# Netzteil.net
KiCad netlist of a schematic drawn in EAGLE
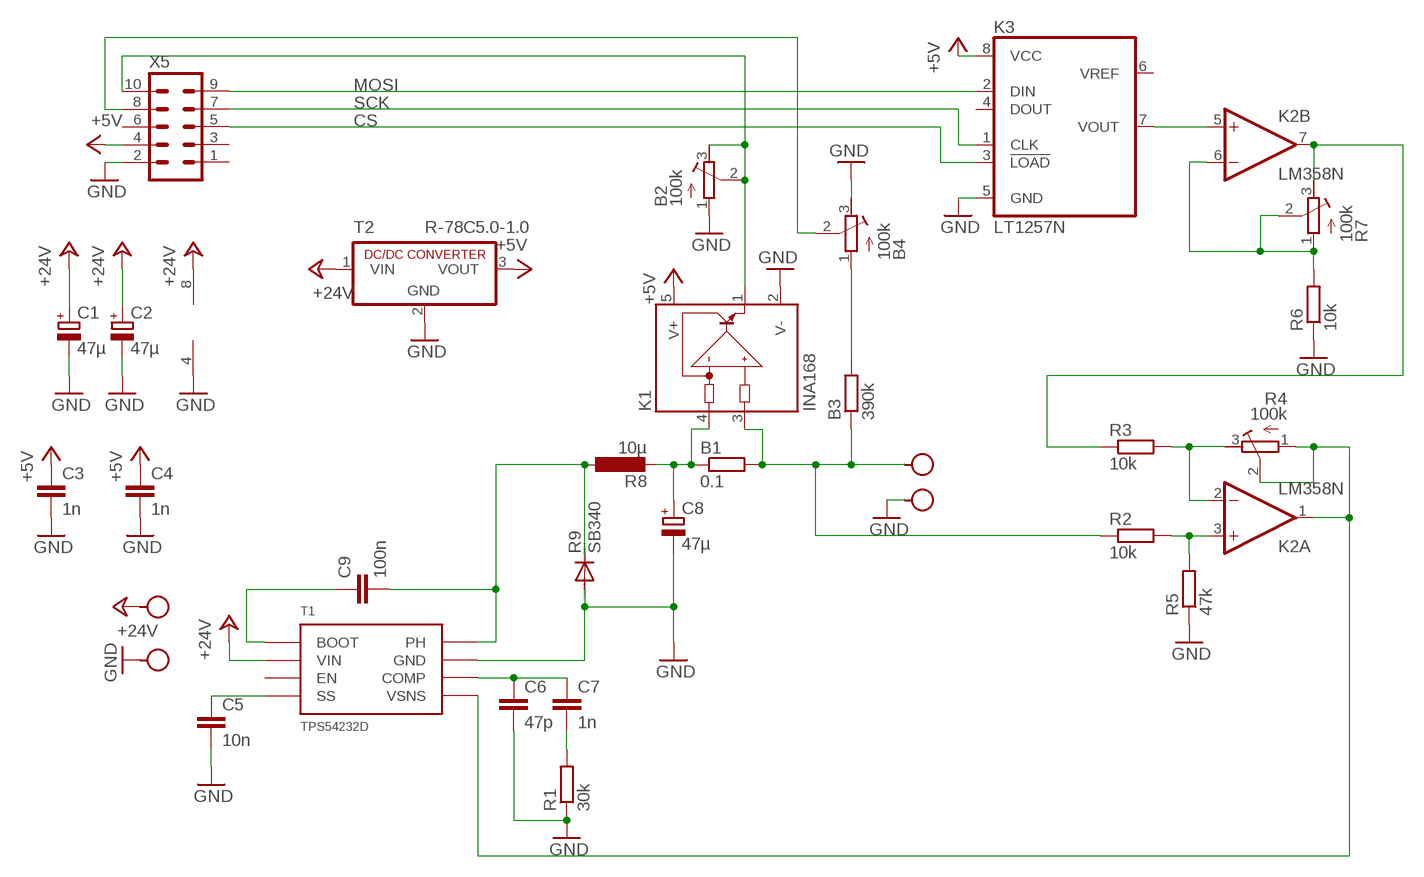
[diagram p0: schematic, sheet 1]

(export (version "E")
  (design (tool "Eeschema 10.0.6"))
  (components
    (comp (ref "B1")
      (value "0.1")
      (footprint "eagle-import:P0817_22")
      (libsource (lib "eagle-import") (part "R-EU_0817/22"))
    )
    (comp (ref "B2")
      (value "100k")
      (footprint "eagle-import:RTRIM64Y")
      (libsource (lib "eagle-import") (part "R-TRIMM64Y"))
    )
    (comp (ref "B3")
      (value "390k")
      (footprint "eagle-import:0309_12")
      (libsource (lib "eagle-import") (part "R-EU_0309/12"))
    )
    (comp (ref "B4")
      (value "100k")
      (footprint "eagle-import:RTRIM64Y")
      (libsource (lib "eagle-import") (part "R-TRIMM64Y"))
    )
    (comp (ref "C1")
      (value "47µ")
      (footprint "eagle-import:E2,5-6")
      (libsource (lib "eagle-import") (part "CPOL-EUE2.5-6"))
    )
    (comp (ref "C2")
      (value "47µ")
      (footprint "eagle-import:E2,5-6")
      (libsource (lib "eagle-import") (part "CPOL-EUE2.5-6"))
    )
    (comp (ref "C3")
      (value "1n")
      (footprint "eagle-import:C025-025X050")
      (libsource (lib "eagle-import") (part "C-EU025-025X050"))
    )
    (comp (ref "C4")
      (value "1n")
      (footprint "eagle-import:C025-025X050")
      (libsource (lib "eagle-import") (part "C-EU025-025X050"))
    )
    (comp (ref "C5")
      (value "10n")
      (footprint "eagle-import:C025-025X050")
      (libsource (lib "eagle-import") (part "C-EU025-025X050"))
    )
    (comp (ref "C6")
      (value "47p")
      (footprint "eagle-import:C025-025X050")
      (libsource (lib "eagle-import") (part "C-EU025-025X050"))
    )
    (comp (ref "C7")
      (value "1n")
      (footprint "eagle-import:C025-025X050")
      (libsource (lib "eagle-import") (part "C-EU025-025X050"))
    )
    (comp (ref "C8")
      (value "47µ")
      (footprint "eagle-import:E2,5-6")
      (libsource (lib "eagle-import") (part "CPOL-EUE2.5-6"))
    )
    (comp (ref "C9")
      (value "100n")
      (footprint "eagle-import:C025-025X050")
      (libsource (lib "eagle-import") (part "C-EU025-025X050"))
    )
    (comp (ref "K1")
      (value "INA168")
      (footprint "eagle-import:SOT23-5")
      (fields (field (name "MF") "TEXAS INSTRUMENTS") (field (name "MPN") "INA168NA/250"))
      (libsource (lib "eagle-import") (part "INA168"))
    )
    (comp (ref "K2")
      (value "LM358N")
      (footprint "eagle-import:DIL08")
      (libsource (lib "eagle-import") (part "LM358N"))
    )
    (comp (ref "K3")
      (value "LT1257N")
      (footprint "eagle-import:DIL08")
      (libsource (lib "eagle-import") (part "LT1257N"))
    )
    (comp (ref "R1")
      (value "30k")
      (footprint "eagle-import:0309_12")
      (libsource (lib "eagle-import") (part "R-EU_0309/12"))
    )
    (comp (ref "R2")
      (value "10k")
      (footprint "eagle-import:0309_12")
      (libsource (lib "eagle-import") (part "R-EU_0309/12"))
    )
    (comp (ref "R3")
      (value "10k")
      (footprint "eagle-import:0309_12")
      (libsource (lib "eagle-import") (part "R-EU_0309/12"))
    )
    (comp (ref "R4")
      (value "100k")
      (footprint "eagle-import:RTRIM64Y")
      (libsource (lib "eagle-import") (part "R-TRIMM64Y"))
    )
    (comp (ref "R5")
      (value "47k")
      (footprint "eagle-import:0309_12")
      (libsource (lib "eagle-import") (part "R-EU_0309/12"))
    )
    (comp (ref "R6")
      (value "10k")
      (footprint "eagle-import:0309_12")
      (libsource (lib "eagle-import") (part "R-EU_0309/12"))
    )
    (comp (ref "R7")
      (value "100k")
      (footprint "eagle-import:RTRIM64Y")
      (libsource (lib "eagle-import") (part "R-TRIMM64Y"))
    )
    (comp (ref "R8")
      (value "10µ")
      (footprint "eagle-import:PIS2816")
      (libsource (lib "eagle-import") (part "L-EUPIS2816"))
    )
    (comp (ref "R9")
      (value "SB340")
      (footprint "eagle-import:DO201-15")
      (libsource (lib "eagle-import") (part "SB320"))
    )
    (comp (ref "T1")
      (value "TPS54232D")
      (footprint "eagle-import:SOIC-8")
      (fields (field (name "MANUFACTURER") "Texas Instruments") (field (name "PART_NUMBER") "TPS54331DR"))
      (libsource (lib "eagle-import") (part "TPS54331DR"))
    )
    (comp (ref "T2")
      (value "R-78C5.0-1.0")
      (footprint "eagle-import:SIP3")
      (fields (field (name "MF") "RECOM POWER"))
      (libsource (lib "eagle-import") (part "R-78C-1.05.0"))
    )
    (comp (ref "X1")
      (value "SEW_HOLE-SMALL")
      (footprint "eagle-import:SIMPLE_HOLE_SM")
      (libsource (lib "eagle-import") (part "SEW_HOLE-SMALL"))
    )
    (comp (ref "X2")
      (value "SEW_HOLE-SMALL")
      (footprint "eagle-import:SIMPLE_HOLE_SM")
      (libsource (lib "eagle-import") (part "SEW_HOLE-SMALL"))
    )
    (comp (ref "X3")
      (value "SEW_HOLE-SMALL")
      (footprint "eagle-import:SIMPLE_HOLE_SM")
      (libsource (lib "eagle-import") (part "SEW_HOLE-SMALL"))
    )
    (comp (ref "X4")
      (value "SEW_HOLE-SMALL")
      (footprint "eagle-import:SIMPLE_HOLE_SM")
      (libsource (lib "eagle-import") (part "SEW_HOLE-SMALL"))
    )
    (comp (ref "X5")
      (value "ML10")
      (footprint "eagle-import:ML10")
      (libsource (lib "eagle-import") (part "ML10"))
    )
  )
  (nets
    (net (code "1") (name "+5V") (class "Default")
      (node (ref "C3") (pin "1") (pinfunction "1_1") (pintype "passive"))
      (node (ref "C4") (pin "1") (pinfunction "1_1") (pintype "passive"))
      (node (ref "K1") (pin "5") (pinfunction "V+_5") (pintype "power_in"))
      (node (ref "K3") (pin "8") (pinfunction "VCC_8") (pintype "power_in"))
      (node (ref "T2") (pin "3") (pinfunction "VOUT_3") (pintype "passive"))
      (node (ref "X5") (pin "4") (pinfunction "4_4") (pintype "passive"))
    )
    (net (code "2") (name "+24V") (class "Default")
      (node (ref "C1") (pin "+") (pinfunction "+_+") (pintype "passive"))
      (node (ref "C2") (pin "+") (pinfunction "+_+") (pintype "passive"))
      (node (ref "K2") (pin "8") (pinfunction "V+_8") (pintype "power_in"))
      (node (ref "T1") (pin "2") (pinfunction "VIN_2") (pintype "input"))
      (node (ref "T2") (pin "1") (pinfunction "VIN_1") (pintype "passive"))
      (node (ref "X1") (pin "P$1") (pinfunction "P$1_P$1") (pintype "bidirectional"))
    )
    (net (code "3") (name "/CS") (class "Default")
      (node (ref "K3") (pin "3") (pinfunction "~{LOAD}_3") (pintype "input"))
      (node (ref "X5") (pin "5") (pinfunction "5_5") (pintype "passive"))
    )
    (net (code "4") (name "/MOSI") (class "Default")
      (node (ref "K3") (pin "2") (pinfunction "DIN_2") (pintype "input"))
      (node (ref "X5") (pin "9") (pinfunction "9_9") (pintype "passive"))
    )
    (net (code "5") (name "/SCK") (class "Default")
      (node (ref "K3") (pin "1") (pinfunction "CLK_1") (pintype "input"))
      (node (ref "X5") (pin "7") (pinfunction "7_7") (pintype "passive"))
    )
    (net (code "6") (name "GND") (class "Default")
      (node (ref "B2") (pin "1") (pinfunction "E_1") (pintype "passive"))
      (node (ref "B4") (pin "3") (pinfunction "A_3") (pintype "passive"))
      (node (ref "C1") (pin "-") (pinfunction "-_-") (pintype "passive"))
      (node (ref "C2") (pin "-") (pinfunction "-_-") (pintype "passive"))
      (node (ref "C3") (pin "2") (pinfunction "2_2") (pintype "passive"))
      (node (ref "C4") (pin "2") (pinfunction "2_2") (pintype "passive"))
      (node (ref "C5") (pin "2") (pinfunction "2_2") (pintype "passive"))
      (node (ref "C6") (pin "2") (pinfunction "2_2") (pintype "passive"))
      (node (ref "C8") (pin "-") (pinfunction "-_-") (pintype "passive"))
      (node (ref "K1") (pin "2") (pinfunction "V-_2") (pintype "power_in"))
      (node (ref "K2") (pin "4") (pinfunction "V-_4") (pintype "power_in"))
      (node (ref "K3") (pin "5") (pinfunction "GND_5") (pintype "power_in"))
      (node (ref "R1") (pin "1") (pinfunction "1_1") (pintype "passive"))
      (node (ref "R5") (pin "1") (pinfunction "1_1") (pintype "passive"))
      (node (ref "R6") (pin "1") (pinfunction "1_1") (pintype "passive"))
      (node (ref "R9") (pin "A") (pinfunction "A_A") (pintype "passive"))
      (node (ref "T1") (pin "7") (pinfunction "GND_7") (pintype "power_in"))
      (node (ref "T2") (pin "2") (pinfunction "GND_2") (pintype "passive"))
      (node (ref "X2") (pin "P$1") (pinfunction "P$1_P$1") (pintype "bidirectional"))
      (node (ref "X4") (pin "P$1") (pinfunction "P$1_P$1") (pintype "bidirectional"))
      (node (ref "X5") (pin "2") (pinfunction "2_2") (pintype "passive"))
    )
    (net (code "7") (name "Net-(B2-A)") (class "Default")
      (node (ref "B2") (pin "2") (pinfunction "S_2") (pintype "passive"))
      (node (ref "B2") (pin "3") (pinfunction "A_3") (pintype "passive"))
      (node (ref "K1") (pin "1") (pinfunction "OUT_1") (pintype "output"))
      (node (ref "X5") (pin "10") (pinfunction "10_10") (pintype "passive"))
    )
    (net (code "8") (name "Net-(B4-E)") (class "Default")
      (node (ref "B3") (pin "2") (pinfunction "2_2") (pintype "passive"))
      (node (ref "B4") (pin "1") (pinfunction "E_1") (pintype "passive"))
    )
    (net (code "9") (name "Net-(B4-S)") (class "Default")
      (node (ref "B4") (pin "2") (pinfunction "S_2") (pintype "passive"))
      (node (ref "X5") (pin "8") (pinfunction "8_8") (pintype "passive"))
    )
    (net (code "10") (name "Net-(C7-Pad2)") (class "Default")
      (node (ref "C7") (pin "2") (pinfunction "2_2") (pintype "passive"))
      (node (ref "R1") (pin "2") (pinfunction "2_2") (pintype "passive"))
    )
    (net (code "11") (name "Net-(K1-IN+)") (class "Default")
      (node (ref "B1") (pin "2") (pinfunction "2_2") (pintype "passive"))
      (node (ref "B3") (pin "1") (pinfunction "1_1") (pintype "passive"))
      (node (ref "K1") (pin "3") (pinfunction "IN+_3") (pintype "input"))
      (node (ref "R2") (pin "1") (pinfunction "1_1") (pintype "passive"))
      (node (ref "X3") (pin "P$1") (pinfunction "P$1_P$1") (pintype "bidirectional"))
    )
    (net (code "12") (name "Net-(K1-IN-)") (class "Default")
      (node (ref "B1") (pin "1") (pinfunction "1_1") (pintype "passive"))
      (node (ref "C8") (pin "+") (pinfunction "+_+") (pintype "passive"))
      (node (ref "K1") (pin "4") (pinfunction "IN-_4") (pintype "input"))
      (node (ref "R8") (pin "2") (pinfunction "2_2") (pintype "passive"))
    )
    (net (code "13") (name "Net-(K2A-+IN)") (class "Default")
      (node (ref "K2") (pin "3") (pinfunction "+IN_3") (pintype "input"))
      (node (ref "R2") (pin "2") (pinfunction "2_2") (pintype "passive"))
      (node (ref "R5") (pin "2") (pinfunction "2_2") (pintype "passive"))
    )
    (net (code "14") (name "Net-(K2A--IN)") (class "Default")
      (node (ref "K2") (pin "2") (pinfunction "-IN_2") (pintype "input"))
      (node (ref "R3") (pin "2") (pinfunction "2_2") (pintype "passive"))
      (node (ref "R4") (pin "3") (pinfunction "A_3") (pintype "passive"))
    )
    (net (code "15") (name "Net-(K2A-OUT)") (class "Default")
      (node (ref "K2") (pin "1") (pinfunction "OUT_1") (pintype "output"))
      (node (ref "R4") (pin "1") (pinfunction "E_1") (pintype "passive"))
      (node (ref "R4") (pin "2") (pinfunction "S_2") (pintype "passive"))
      (node (ref "T1") (pin "5") (pinfunction "VSNS_5") (pintype "input"))
    )
    (net (code "16") (name "Net-(K2B-+IN)") (class "Default")
      (node (ref "K2") (pin "5") (pinfunction "+IN_5") (pintype "input"))
      (node (ref "K3") (pin "7") (pinfunction "VOUT_7") (pintype "output"))
    )
    (net (code "17") (name "Net-(K2B--IN)") (class "Default")
      (node (ref "K2") (pin "6") (pinfunction "-IN_6") (pintype "input"))
      (node (ref "R6") (pin "2") (pinfunction "2_2") (pintype "passive"))
      (node (ref "R7") (pin "1") (pinfunction "E_1") (pintype "passive"))
      (node (ref "R7") (pin "2") (pinfunction "S_2") (pintype "passive"))
    )
    (net (code "18") (name "Net-(K2B-OUT)") (class "Default")
      (node (ref "K2") (pin "7") (pinfunction "OUT_7") (pintype "output"))
      (node (ref "R3") (pin "1") (pinfunction "1_1") (pintype "passive"))
      (node (ref "R7") (pin "3") (pinfunction "A_3") (pintype "passive"))
    )
    (net (code "19") (name "Net-(T1-BOOT)") (class "Default")
      (node (ref "C9") (pin "1") (pinfunction "1_1") (pintype "passive"))
      (node (ref "T1") (pin "1") (pinfunction "BOOT_1") (pintype "bidirectional"))
    )
    (net (code "20") (name "Net-(T1-COMP)") (class "Default")
      (node (ref "C6") (pin "1") (pinfunction "1_1") (pintype "passive"))
      (node (ref "C7") (pin "1") (pinfunction "1_1") (pintype "passive"))
      (node (ref "T1") (pin "6") (pinfunction "COMP_6") (pintype "bidirectional"))
    )
    (net (code "21") (name "Net-(T1-PH)") (class "Default")
      (node (ref "C9") (pin "2") (pinfunction "2_2") (pintype "passive"))
      (node (ref "R8") (pin "1") (pinfunction "1_1") (pintype "passive"))
      (node (ref "R9") (pin "C") (pinfunction "C_C") (pintype "passive"))
      (node (ref "T1") (pin "8") (pinfunction "PH_8") (pintype "bidirectional"))
    )
    (net (code "22") (name "Net-(T1-SS)") (class "Default")
      (node (ref "C5") (pin "1") (pinfunction "1_1") (pintype "passive"))
      (node (ref "T1") (pin "4") (pinfunction "SS_4") (pintype "bidirectional"))
    )
    (net (code "23") (name "unconnected-(K3-DOUT-Pad4)") (class "Default")
      (node (ref "K3") (pin "4") (pinfunction "DOUT_4") (pintype "output"))
    )
    (net (code "24") (name "unconnected-(K3-VREF-Pad6)") (class "Default")
      (node (ref "K3") (pin "6") (pinfunction "VREF_6") (pintype "input"))
    )
    (net (code "25") (name "unconnected-(T1-EN-Pad3)") (class "Default")
      (node (ref "T1") (pin "3") (pinfunction "EN_3") (pintype "input"))
    )
    (net (code "26") (name "unconnected-(X5-Pad1)") (class "Default")
      (node (ref "X5") (pin "1") (pinfunction "1_1") (pintype "passive"))
    )
    (net (code "27") (name "unconnected-(X5-Pad3)") (class "Default")
      (node (ref "X5") (pin "3") (pinfunction "3_3") (pintype "passive"))
    )
    (net (code "28") (name "unconnected-(X5-Pad6)") (class "Default")
      (node (ref "X5") (pin "6") (pinfunction "6_6") (pintype "passive"))
    )
  )
)
